# Adafruit_STEMMA_Analog_SPDT_Switch.net
KiCad netlist of a schematic drawn in EAGLE
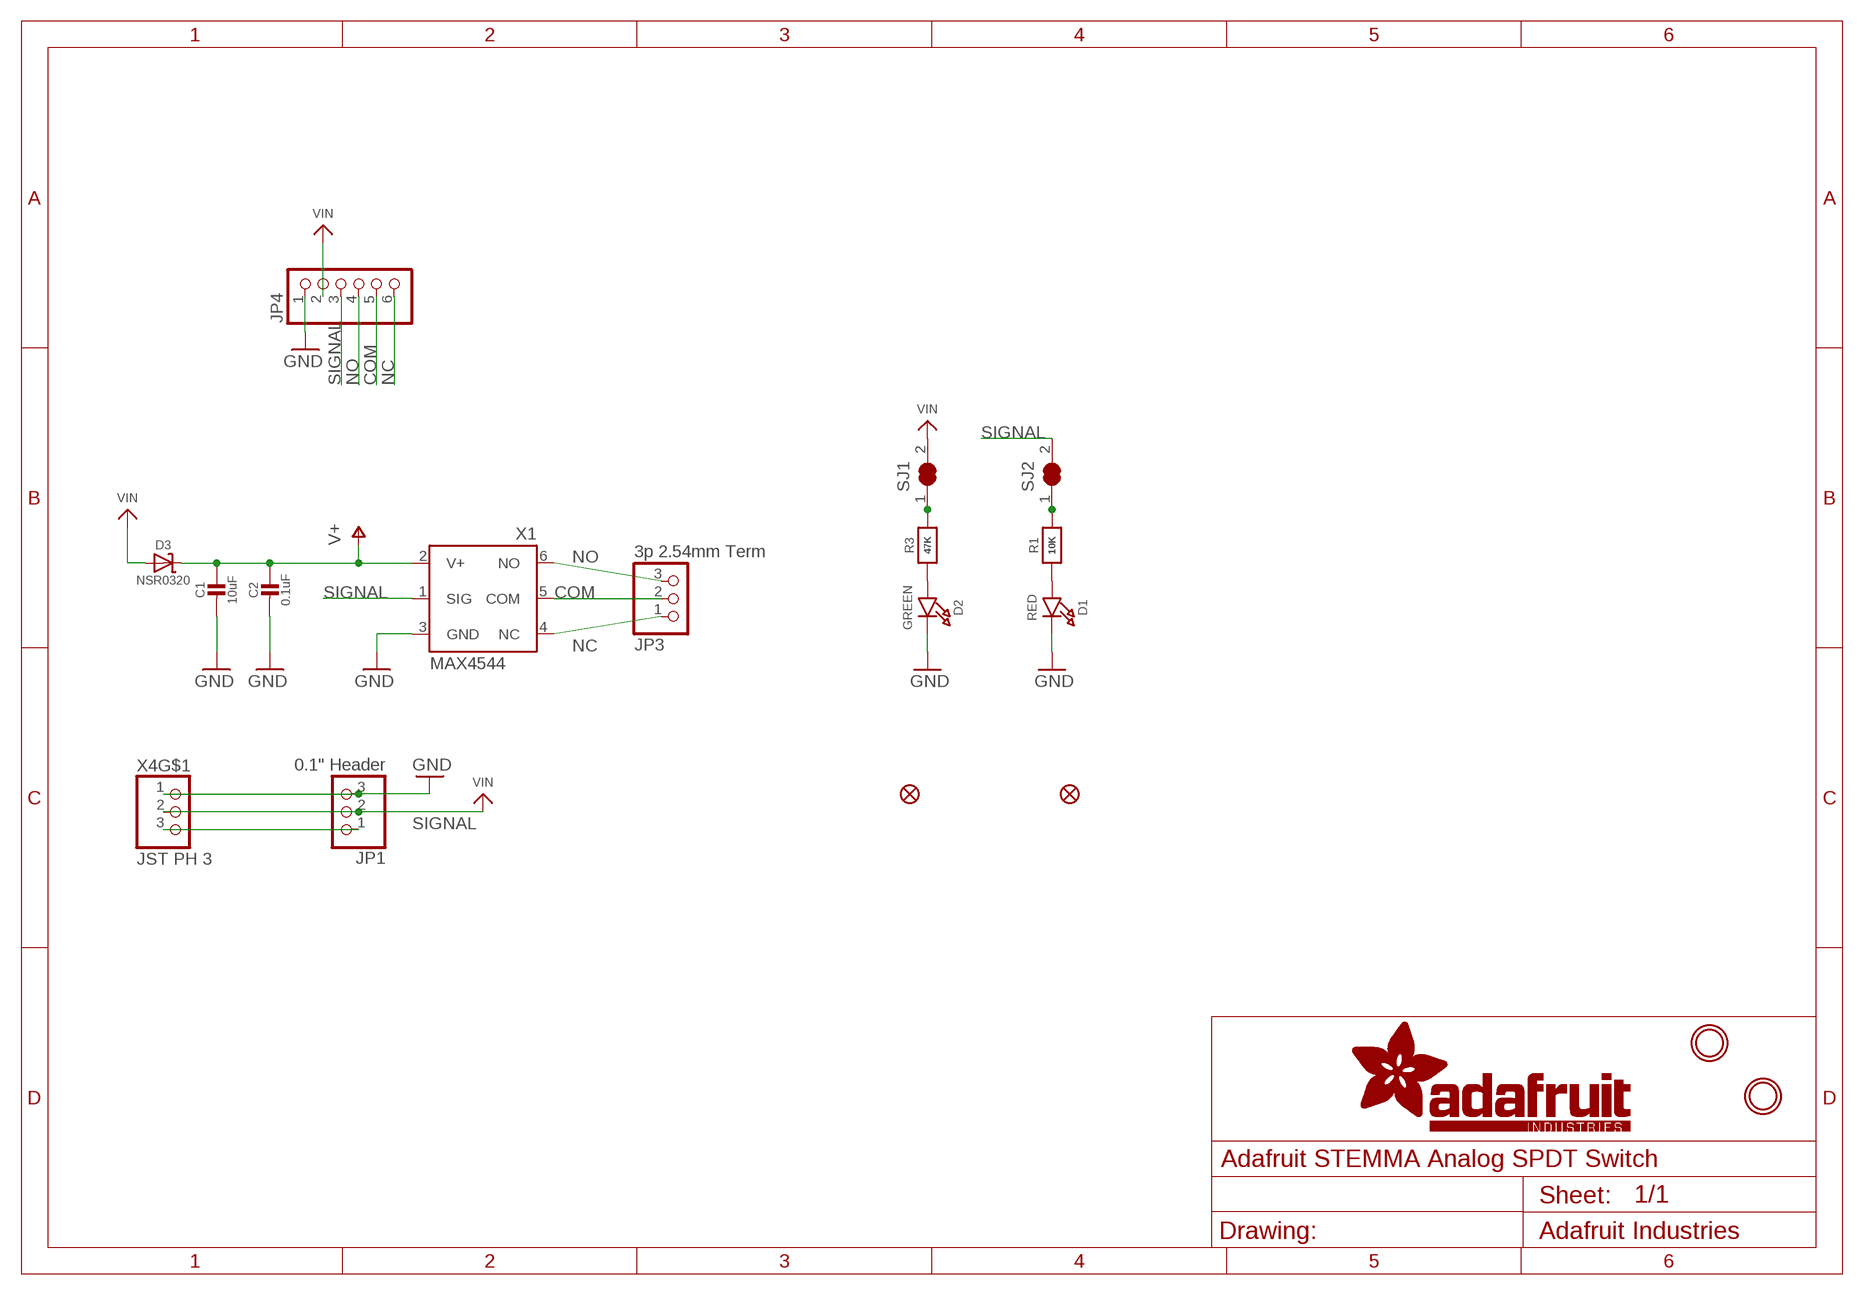
[diagram p0: schematic, sheet 1]

(export (version "E")
  (design (tool "Eeschema 10.0.6"))
  (components
    (comp (ref "C1")
      (value "10uF")
      (footprint "eagle-import:0805-NO")
      (libsource (lib "eagle-import") (part "CAP_CERAMIC0805-NOOUTLINE"))
    )
    (comp (ref "C2")
      (value "0.1uF")
      (footprint "eagle-import:0603-NO")
      (libsource (lib "eagle-import") (part "CAP_CERAMIC0603_NO"))
    )
    (comp (ref "D1")
      (value "RED")
      (footprint "eagle-import:CHIPLED_0603_NOOUTLINE")
      (libsource (lib "eagle-import") (part "LED0603_NOOUTLINE"))
    )
    (comp (ref "D2")
      (value "GREEN")
      (footprint "eagle-import:CHIPLED_0603_NOOUTLINE")
      (libsource (lib "eagle-import") (part "LED0603_NOOUTLINE"))
    )
    (comp (ref "D3")
      (value "NSR0320")
      (footprint "eagle-import:SOD-323")
      (libsource (lib "eagle-import") (part "DIODE-SCHOTTKYSOD-323"))
    )
    (comp (ref "FID2")
      (value "FIDUCIAL_1MM")
      (footprint "eagle-import:FIDUCIAL_1MM")
      (libsource (lib "eagle-import") (part "FIDUCIAL_1MM"))
    )
    (comp (ref "FID3")
      (value "FIDUCIAL_1MM")
      (footprint "eagle-import:FIDUCIAL_1MM")
      (libsource (lib "eagle-import") (part "FIDUCIAL_1MM"))
    )
    (comp (ref "JP1")
      (value "0.1\" Header")
      (footprint "eagle-import:1X03_OVAL")
      (libsource (lib "eagle-import") (part "HEADER-1X3"))
    )
    (comp (ref "JP3")
      (value "3p 2.54mm Term")
      (footprint "eagle-import:1X03_2.54MMTERMINAL")
      (libsource (lib "eagle-import") (part "HEADER-1X3_254TERM"))
    )
    (comp (ref "JP4")
      (value "HEADER-1X676MIL_FULLROUND")
      (footprint "eagle-import:1X06_ROUND_FULL_76")
      (libsource (lib "eagle-import") (part "HEADER-1X676MIL_FULLROUND"))
    )
    (comp (ref "R1")
      (value "10K")
      (footprint "eagle-import:0603-NO")
      (libsource (lib "eagle-import") (part "RESISTOR_0603_NOOUT"))
    )
    (comp (ref "R3")
      (value "47K")
      (footprint "eagle-import:0603-NO")
      (libsource (lib "eagle-import") (part "RESISTOR_0603_NOOUT"))
    )
    (comp (ref "SJ1")
      (value "SOLDERJUMPER_CLOSED")
      (footprint "eagle-import:SOLDERJUMPER_CLOSEDWIRE")
      (libsource (lib "eagle-import") (part "SOLDERJUMPER_CLOSED"))
    )
    (comp (ref "SJ2")
      (value "SOLDERJUMPER_CLOSED")
      (footprint "eagle-import:SOLDERJUMPER_CLOSEDWIRE")
      (libsource (lib "eagle-import") (part "SOLDERJUMPER_CLOSED"))
    )
    (comp (ref "U$1")
      (value "MOUNTINGHOLE2.5")
      (footprint "eagle-import:MOUNTINGHOLE_2.5_PLATED")
      (libsource (lib "eagle-import") (part "MOUNTINGHOLE2.5"))
    )
    (comp (ref "U$8")
      (value "MOUNTINGHOLE2.5")
      (footprint "eagle-import:MOUNTINGHOLE_2.5_PLATED")
      (libsource (lib "eagle-import") (part "MOUNTINGHOLE2.5"))
    )
    (comp (ref "X1")
      (value "MAX4544")
      (footprint "eagle-import:SOT23-6")
      (libsource (lib "eagle-import") (part "COS4561"))
    )
    (comp (ref "X4")
      (value "JST PH 3")
      (footprint "eagle-import:JSTPH3")
      (libsource (lib "eagle-import") (part "CON_JST_PH_3PIN"))
    )
  )
  (nets
    (net (code "1") (name "/COM") (class "Default")
      (node (ref "JP3") (pin "2") (pinfunction "2_2") (pintype "passive"))
      (node (ref "JP4") (pin "5") (pinfunction "5_5") (pintype "passive"))
      (node (ref "X1") (pin "5") (pinfunction "COM_5") (pintype "bidirectional"))
    )
    (net (code "2") (name "/NC") (class "Default")
      (node (ref "JP3") (pin "1") (pinfunction "1_1") (pintype "passive"))
      (node (ref "JP4") (pin "6") (pinfunction "6_6") (pintype "passive"))
      (node (ref "X1") (pin "4") (pinfunction "NC_4") (pintype "bidirectional"))
    )
    (net (code "3") (name "/NO") (class "Default")
      (node (ref "JP3") (pin "3") (pinfunction "3_3") (pintype "passive"))
      (node (ref "JP4") (pin "4") (pinfunction "4_4") (pintype "passive"))
      (node (ref "X1") (pin "6") (pinfunction "NO_6") (pintype "bidirectional"))
    )
    (net (code "4") (name "/SIGNAL") (class "Default")
      (node (ref "JP1") (pin "1") (pinfunction "1_1") (pintype "passive"))
      (node (ref "JP4") (pin "3") (pinfunction "3_3") (pintype "passive"))
      (node (ref "SJ2") (pin "2") (pinfunction "2_2") (pintype "passive"))
      (node (ref "X1") (pin "1") (pinfunction "SIG_1") (pintype "input"))
      (node (ref "X4") (pin "3") (pinfunction "3_3") (pintype "passive"))
    )
    (net (code "5") (name "GND") (class "Default")
      (node (ref "C1") (pin "2") (pinfunction "2_2") (pintype "passive"))
      (node (ref "C2") (pin "2") (pinfunction "2_2") (pintype "passive"))
      (node (ref "D1") (pin "C") (pinfunction "C_C") (pintype "passive"))
      (node (ref "D2") (pin "C") (pinfunction "C_C") (pintype "passive"))
      (node (ref "JP1") (pin "3") (pinfunction "3_3") (pintype "passive"))
      (node (ref "JP4") (pin "1") (pinfunction "1_1") (pintype "passive"))
      (node (ref "X1") (pin "3") (pinfunction "GND_3") (pintype "power_in"))
      (node (ref "X4") (pin "1") (pinfunction "1_1") (pintype "passive"))
    )
    (net (code "6") (name "Net-(D1-PadA)") (class "Default")
      (node (ref "D1") (pin "A") (pinfunction "A_A") (pintype "passive"))
      (node (ref "R1") (pin "1") (pinfunction "1_1") (pintype "passive"))
    )
    (net (code "7") (name "Net-(D2-PadA)") (class "Default")
      (node (ref "D2") (pin "A") (pinfunction "A_A") (pintype "passive"))
      (node (ref "R3") (pin "1") (pinfunction "1_1") (pintype "passive"))
    )
    (net (code "8") (name "Net-(R1-Pad2)") (class "Default")
      (node (ref "R1") (pin "2") (pinfunction "2_2") (pintype "passive"))
      (node (ref "SJ2") (pin "1") (pinfunction "1_1") (pintype "passive"))
    )
    (net (code "9") (name "Net-(R3-Pad2)") (class "Default")
      (node (ref "R3") (pin "2") (pinfunction "2_2") (pintype "passive"))
      (node (ref "SJ1") (pin "1") (pinfunction "1_1") (pintype "passive"))
    )
    (net (code "10") (name "V+") (class "Default")
      (node (ref "C1") (pin "1") (pinfunction "1_1") (pintype "passive"))
      (node (ref "C2") (pin "1") (pinfunction "1_1") (pintype "passive"))
      (node (ref "D3") (pin "C") (pinfunction "C_C") (pintype "passive"))
      (node (ref "X1") (pin "2") (pinfunction "V+_2") (pintype "power_in"))
    )
    (net (code "11") (name "VIN") (class "Default")
      (node (ref "D3") (pin "A") (pinfunction "A_A") (pintype "passive"))
      (node (ref "JP1") (pin "2") (pinfunction "2_2") (pintype "passive"))
      (node (ref "JP4") (pin "2") (pinfunction "2_2") (pintype "passive"))
      (node (ref "SJ1") (pin "2") (pinfunction "2_2") (pintype "passive"))
      (node (ref "X4") (pin "2") (pinfunction "2_2") (pintype "passive"))
    )
  )
)
